# BBBL-CAN-Motor-Interface.net
KiCad netlist of a schematic drawn in EAGLE
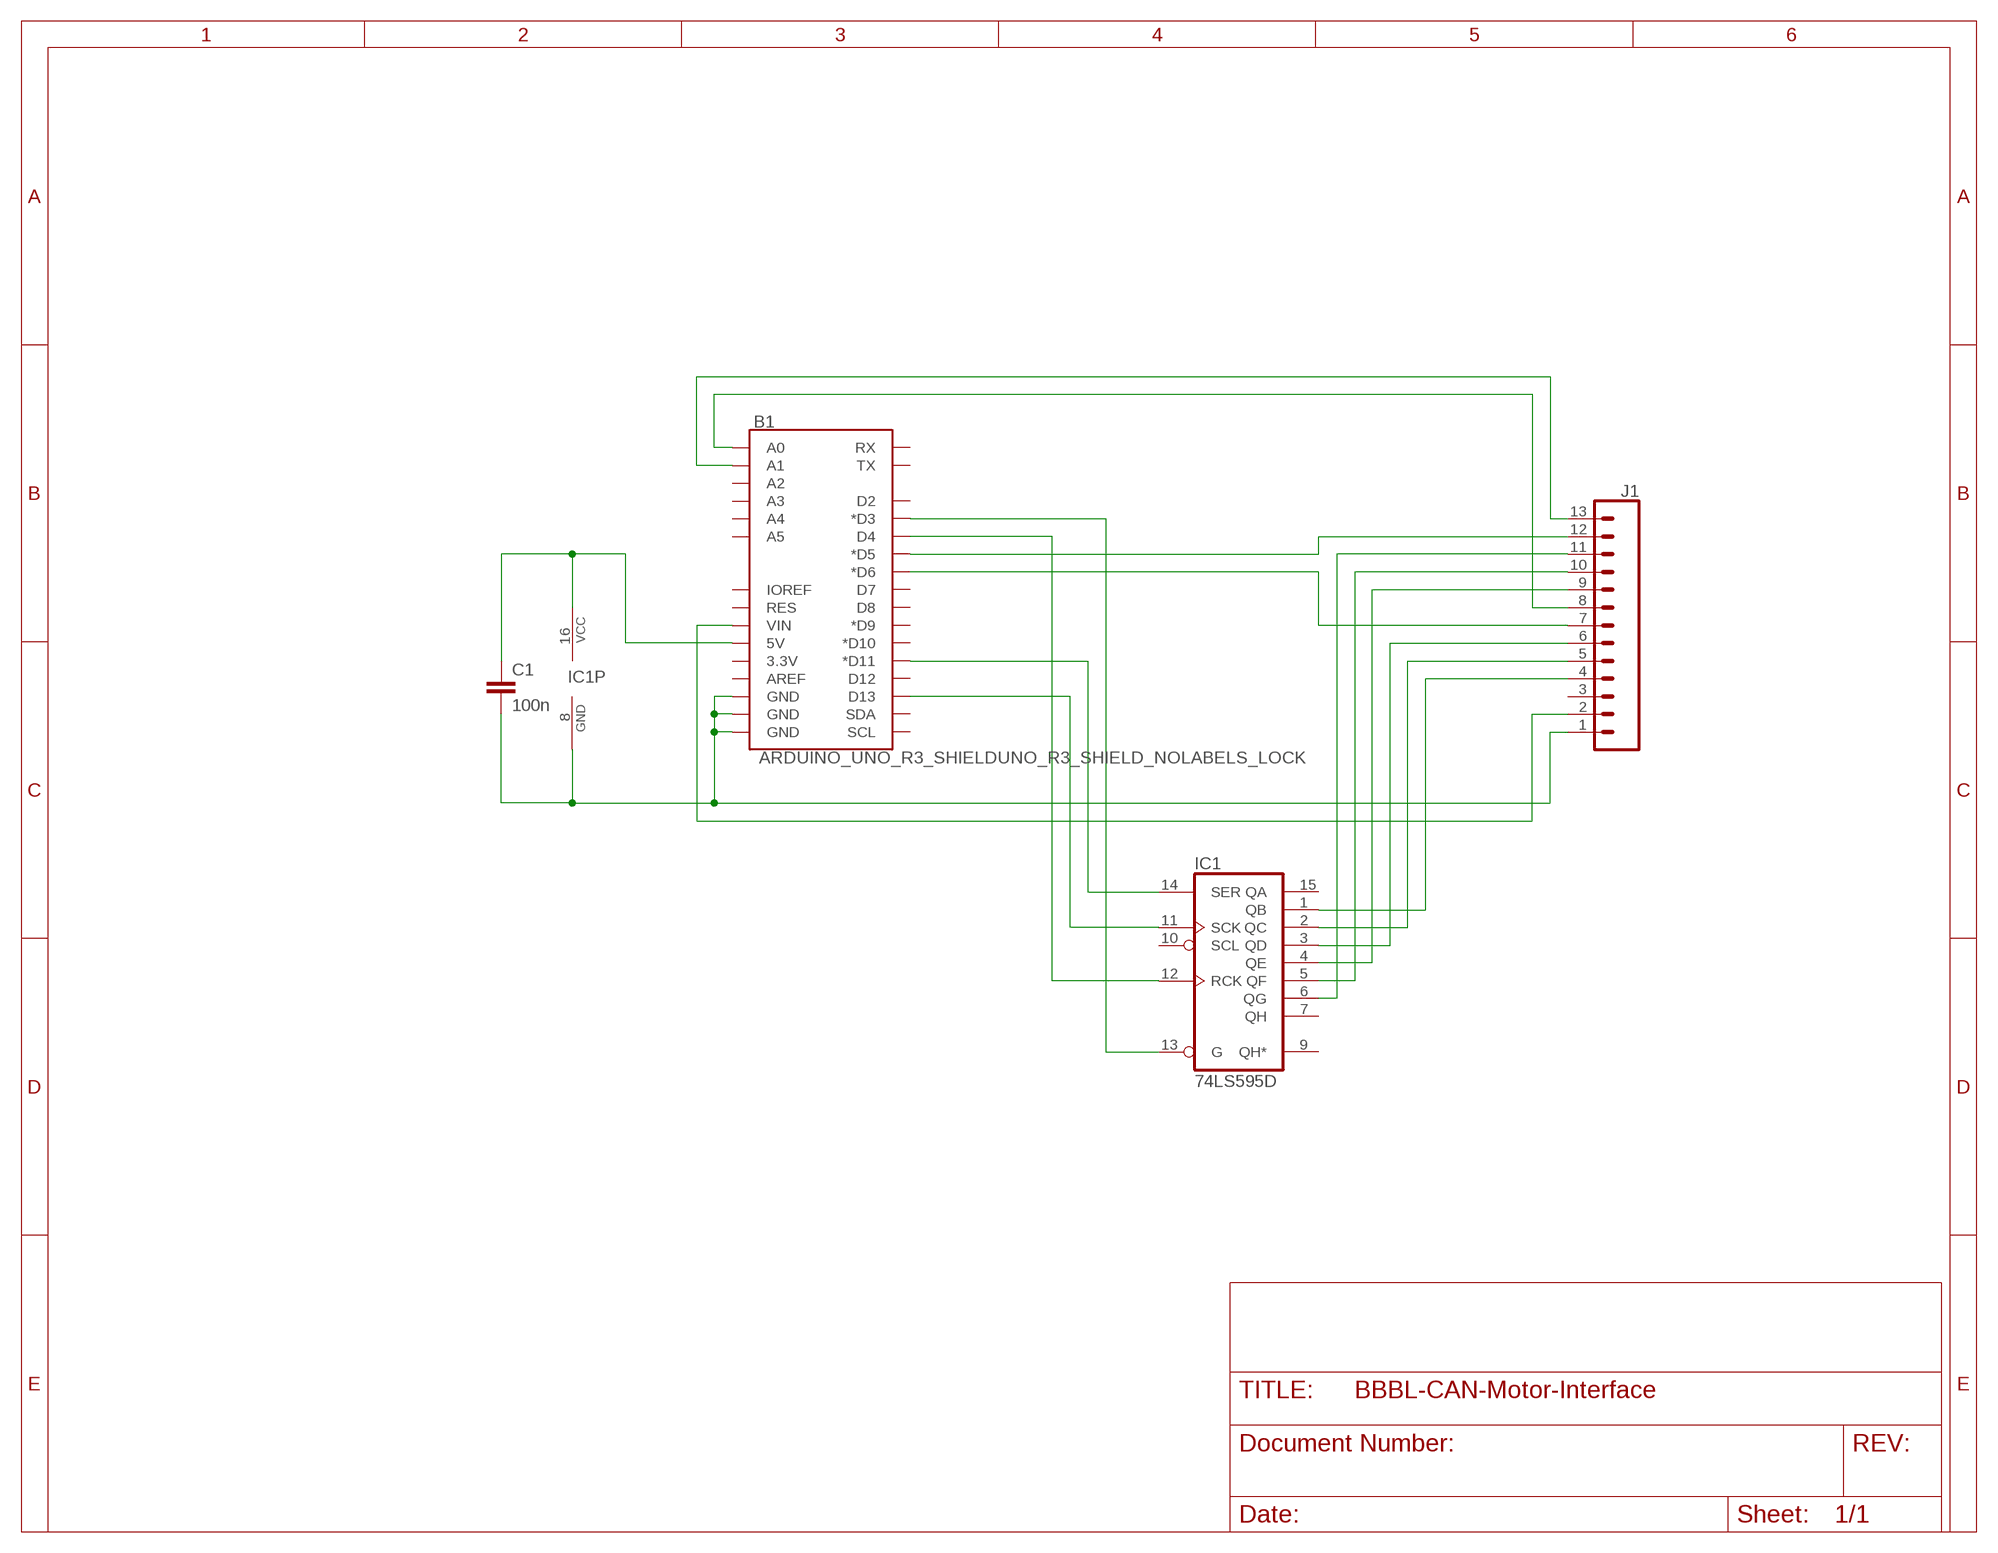
[diagram p0: schematic, sheet 1]

(export (version "E")
  (design (tool "Eeschema 10.0.6"))
  (components
    (comp (ref "B1")
      (value "ARDUINO_UNO_R3_SHIELDUNO_R3_SHIELD_NOLABELS_LOCK")
      (footprint "eagle-import:UNO_R3_SHIELD_NOLABELS_LOCK")
      (libsource (lib "eagle-import") (part "ARDUINO_UNO_R3_SHIELDUNO_R3_SHIELD_NOLABELS_LOCK"))
    )
    (comp (ref "C1")
      (value "100n")
      (footprint "eagle-import:C0603")
      (libsource (lib "eagle-import") (part "C-EUC0603"))
    )
    (comp (ref "IC1")
      (value "74LS595D")
      (footprint "eagle-import:SO16")
      (libsource (lib "eagle-import") (part "74595DLS"))
    )
    (comp (ref "J1")
      (value "CONN_13LOCK")
      (footprint "eagle-import:1X13_LOCK")
      (libsource (lib "eagle-import") (part "CONN_13LOCK"))
    )
  )
  (nets
    (net (code "1") (name "Net-(B1-*D3)") (class "Default")
      (node (ref "B1") (pin "D3") (pinfunction "*D3_D3") (pintype "bidirectional"))
      (node (ref "IC1") (pin "13") (pinfunction "G_13") (pintype "input"))
    )
    (net (code "2") (name "Net-(B1-*D5)") (class "Default")
      (node (ref "B1") (pin "D5") (pinfunction "*D5_D5") (pintype "bidirectional"))
      (node (ref "J1") (pin "12") (pinfunction "12_12") (pintype "passive"))
    )
    (net (code "3") (name "Net-(B1-*D6)") (class "Default")
      (node (ref "B1") (pin "D6") (pinfunction "*D6_D6") (pintype "bidirectional"))
      (node (ref "J1") (pin "7") (pinfunction "7_7") (pintype "passive"))
    )
    (net (code "4") (name "Net-(B1-*D11)") (class "Default")
      (node (ref "B1") (pin "D11") (pinfunction "*D11_D11") (pintype "bidirectional"))
      (node (ref "IC1") (pin "14") (pinfunction "SER_14") (pintype "input"))
    )
    (net (code "5") (name "Net-(B1-PadA0)") (class "Default")
      (node (ref "B1") (pin "A0") (pinfunction "A0_A0") (pintype "bidirectional"))
      (node (ref "J1") (pin "8") (pinfunction "8_8") (pintype "passive"))
    )
    (net (code "6") (name "Net-(B1-PadA1)") (class "Default")
      (node (ref "B1") (pin "A1") (pinfunction "A1_A1") (pintype "bidirectional"))
      (node (ref "J1") (pin "13") (pinfunction "13_13") (pintype "passive"))
    )
    (net (code "7") (name "Net-(B1-PadVIN)") (class "Default")
      (node (ref "B1") (pin "VIN") (pinfunction "VIN_VIN") (pintype "bidirectional"))
      (node (ref "J1") (pin "2") (pinfunction "2_2") (pintype "passive"))
    )
    (net (code "8") (name "Net-(IC1A-QB)") (class "Default")
      (node (ref "IC1") (pin "1") (pinfunction "QB_1") (pintype "tri_state"))
      (node (ref "J1") (pin "4") (pinfunction "4_4") (pintype "passive"))
    )
    (net (code "9") (name "Net-(IC1A-QC)") (class "Default")
      (node (ref "IC1") (pin "2") (pinfunction "QC_2") (pintype "tri_state"))
      (node (ref "J1") (pin "5") (pinfunction "5_5") (pintype "passive"))
    )
    (net (code "10") (name "Net-(IC1A-QD)") (class "Default")
      (node (ref "IC1") (pin "3") (pinfunction "QD_3") (pintype "tri_state"))
      (node (ref "J1") (pin "6") (pinfunction "6_6") (pintype "passive"))
    )
    (net (code "11") (name "Net-(IC1A-QE)") (class "Default")
      (node (ref "IC1") (pin "4") (pinfunction "QE_4") (pintype "tri_state"))
      (node (ref "J1") (pin "9") (pinfunction "9_9") (pintype "passive"))
    )
    (net (code "12") (name "Net-(IC1A-QF)") (class "Default")
      (node (ref "IC1") (pin "5") (pinfunction "QF_5") (pintype "tri_state"))
      (node (ref "J1") (pin "10") (pinfunction "10_10") (pintype "passive"))
    )
    (net (code "13") (name "Net-(IC1A-QG)") (class "Default")
      (node (ref "IC1") (pin "6") (pinfunction "QG_6") (pintype "tri_state"))
      (node (ref "J1") (pin "11") (pinfunction "11_11") (pintype "passive"))
    )
    (net (code "14") (name "Net-(IC1A-RCK)") (class "Default")
      (node (ref "B1") (pin "D4") (pinfunction "D4_D4") (pintype "bidirectional"))
      (node (ref "IC1") (pin "12") (pinfunction "RCK_12") (pintype "input"))
    )
    (net (code "15") (name "Net-(IC1A-SCK)") (class "Default")
      (node (ref "B1") (pin "D13") (pinfunction "D13_D13") (pintype "bidirectional"))
      (node (ref "IC1") (pin "11") (pinfunction "SCK_11") (pintype "input"))
    )
    (net (code "16") (name "Net-(IC1B-GND)") (class "Default")
      (node (ref "B1") (pin "GND@0") (pinfunction "GND_GND@0") (pintype "bidirectional"))
      (node (ref "B1") (pin "GND@1") (pinfunction "GND_GND@1") (pintype "bidirectional"))
      (node (ref "B1") (pin "GND@2") (pinfunction "GND_GND@2") (pintype "bidirectional"))
      (node (ref "C1") (pin "2") (pinfunction "2_2") (pintype "passive"))
      (node (ref "IC1") (pin "8") (pinfunction "GND_8") (pintype "power_in"))
      (node (ref "J1") (pin "1") (pinfunction "1_1") (pintype "passive"))
    )
    (net (code "17") (name "Net-(IC1B-VCC)") (class "Default")
      (node (ref "B1") (pin "5V") (pinfunction "5V_5V") (pintype "bidirectional"))
      (node (ref "C1") (pin "1") (pinfunction "1_1") (pintype "passive"))
      (node (ref "IC1") (pin "16") (pinfunction "VCC_16") (pintype "power_in"))
    )
    (net (code "18") (name "unconnected-(B1-*D9-PadD9)") (class "Default")
      (node (ref "B1") (pin "D9") (pinfunction "*D9_D9") (pintype "bidirectional"))
    )
    (net (code "19") (name "unconnected-(B1-*D10-PadD10)") (class "Default")
      (node (ref "B1") (pin "D10") (pinfunction "*D10_D10") (pintype "bidirectional"))
    )
    (net (code "20") (name "unconnected-(B1-Pad3.3V)") (class "Default")
      (node (ref "B1") (pin "3.3V") (pinfunction "3.3V_3.3V") (pintype "bidirectional"))
    )
    (net (code "21") (name "unconnected-(B1-PadA2)") (class "Default")
      (node (ref "B1") (pin "A2") (pinfunction "A2_A2") (pintype "bidirectional"))
    )
    (net (code "22") (name "unconnected-(B1-PadA3)") (class "Default")
      (node (ref "B1") (pin "A3") (pinfunction "A3_A3") (pintype "bidirectional"))
    )
    (net (code "23") (name "unconnected-(B1-PadA4)") (class "Default")
      (node (ref "B1") (pin "A4") (pinfunction "A4_A4") (pintype "bidirectional"))
    )
    (net (code "24") (name "unconnected-(B1-PadA5)") (class "Default")
      (node (ref "B1") (pin "A5") (pinfunction "A5_A5") (pintype "bidirectional"))
    )
    (net (code "25") (name "unconnected-(B1-PadAREF)") (class "Default")
      (node (ref "B1") (pin "AREF") (pinfunction "AREF_AREF") (pintype "bidirectional"))
    )
    (net (code "26") (name "unconnected-(B1-PadD2)") (class "Default")
      (node (ref "B1") (pin "D2") (pinfunction "D2_D2") (pintype "bidirectional"))
    )
    (net (code "27") (name "unconnected-(B1-PadD7)") (class "Default")
      (node (ref "B1") (pin "D7") (pinfunction "D7_D7") (pintype "bidirectional"))
    )
    (net (code "28") (name "unconnected-(B1-PadD8)") (class "Default")
      (node (ref "B1") (pin "D8") (pinfunction "D8_D8") (pintype "bidirectional"))
    )
    (net (code "29") (name "unconnected-(B1-PadD12)") (class "Default")
      (node (ref "B1") (pin "D12") (pinfunction "D12_D12") (pintype "bidirectional"))
    )
    (net (code "30") (name "unconnected-(B1-PadIOREF)") (class "Default")
      (node (ref "B1") (pin "IOREF") (pinfunction "IOREF_IOREF") (pintype "bidirectional"))
    )
    (net (code "31") (name "unconnected-(B1-PadRES)") (class "Default")
      (node (ref "B1") (pin "RES") (pinfunction "RES_RES") (pintype "bidirectional"))
    )
    (net (code "32") (name "unconnected-(B1-PadRX)") (class "Default")
      (node (ref "B1") (pin "RX") (pinfunction "RX_RX") (pintype "bidirectional"))
    )
    (net (code "33") (name "unconnected-(B1-PadSCL)") (class "Default")
      (node (ref "B1") (pin "SCL") (pinfunction "SCL_SCL") (pintype "bidirectional"))
    )
    (net (code "34") (name "unconnected-(B1-PadSDA)") (class "Default")
      (node (ref "B1") (pin "SDA") (pinfunction "SDA_SDA") (pintype "bidirectional"))
    )
    (net (code "35") (name "unconnected-(B1-PadTX)") (class "Default")
      (node (ref "B1") (pin "TX") (pinfunction "TX_TX") (pintype "bidirectional"))
    )
    (net (code "36") (name "unconnected-(IC1A-QA-Pad15)") (class "Default")
      (node (ref "IC1") (pin "15") (pinfunction "QA_15") (pintype "tri_state"))
    )
    (net (code "37") (name "unconnected-(IC1A-QH*-Pad9)") (class "Default")
      (node (ref "IC1") (pin "9") (pinfunction "QH*_9") (pintype "tri_state"))
    )
    (net (code "38") (name "unconnected-(IC1A-QH-Pad7)") (class "Default")
      (node (ref "IC1") (pin "7") (pinfunction "QH_7") (pintype "tri_state"))
    )
    (net (code "39") (name "unconnected-(IC1A-SCL-Pad10)") (class "Default")
      (node (ref "IC1") (pin "10") (pinfunction "SCL_10") (pintype "input"))
    )
    (net (code "40") (name "unconnected-(J1-Pad3)") (class "Default")
      (node (ref "J1") (pin "3") (pinfunction "3_3") (pintype "passive"))
    )
  )
)
